# IFE_TSAL_Light_2019_v1_0.net
KiCad netlist of a schematic drawn in EAGLE
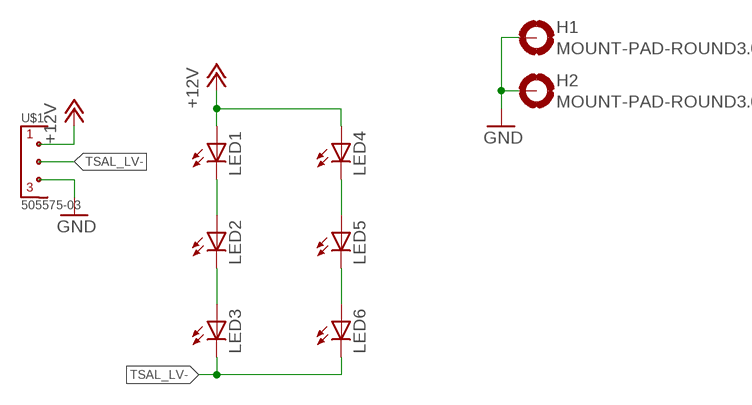
[diagram p0: schematic, sheet 1]

(export (version "E")
  (design (tool "Eeschema 10.0.6"))
  (components
    (comp (ref "H1")
      (value "MOUNT-PAD-ROUND3.0")
      (footprint "eagle-import:3,0-PAD")
      (libsource (lib "eagle-import") (part "MOUNT-PAD-ROUND3.0"))
    )
    (comp (ref "H2")
      (value "MOUNT-PAD-ROUND3.0")
      (footprint "eagle-import:3,0-PAD")
      (libsource (lib "eagle-import") (part "MOUNT-PAD-ROUND3.0"))
    )
    (comp (ref "LED1")
      (value "LED5MM")
      (footprint "eagle-import:LED5MM")
      (libsource (lib "eagle-import") (part "LED5MM"))
    )
    (comp (ref "LED2")
      (value "LED5MM")
      (footprint "eagle-import:LED5MM")
      (libsource (lib "eagle-import") (part "LED5MM"))
    )
    (comp (ref "LED3")
      (value "LED5MM")
      (footprint "eagle-import:LED5MM")
      (libsource (lib "eagle-import") (part "LED5MM"))
    )
    (comp (ref "LED4")
      (value "LED5MM")
      (footprint "eagle-import:LED5MM")
      (libsource (lib "eagle-import") (part "LED5MM"))
    )
    (comp (ref "LED5")
      (value "LED5MM")
      (footprint "eagle-import:LED5MM")
      (libsource (lib "eagle-import") (part "LED5MM"))
    )
    (comp (ref "LED6")
      (value "LED5MM")
      (footprint "eagle-import:LED5MM")
      (libsource (lib "eagle-import") (part "LED5MM"))
    )
    (comp (ref "U$1")
      (value "505575-03")
      (footprint "eagle-import:505575-03")
      (libsource (lib "eagle-import") (part "505575-03"))
    )
  )
  (nets
    (net (code "1") (name "+12V") (class "Default")
      (node (ref "LED1") (pin "A") (pinfunction "A_A") (pintype "passive"))
      (node (ref "LED4") (pin "A") (pinfunction "A_A") (pintype "passive"))
      (node (ref "U$1") (pin "1") (pinfunction "1_1") (pintype "bidirectional"))
    )
    (net (code "2") (name "GND") (class "Default")
      (node (ref "H1") (pin "B3,0") (pinfunction "MOUNT_B3,0") (pintype "passive"))
      (node (ref "H2") (pin "B3,0") (pinfunction "MOUNT_B3,0") (pintype "passive"))
      (node (ref "U$1") (pin "3") (pinfunction "3_3") (pintype "bidirectional"))
    )
    (net (code "3") (name "Net-(LED1-C)") (class "Default")
      (node (ref "LED1") (pin "K") (pinfunction "C_K") (pintype "passive"))
      (node (ref "LED2") (pin "A") (pinfunction "A_A") (pintype "passive"))
    )
    (net (code "4") (name "Net-(LED2-C)") (class "Default")
      (node (ref "LED2") (pin "K") (pinfunction "C_K") (pintype "passive"))
      (node (ref "LED3") (pin "A") (pinfunction "A_A") (pintype "passive"))
    )
    (net (code "5") (name "Net-(LED4-C)") (class "Default")
      (node (ref "LED4") (pin "K") (pinfunction "C_K") (pintype "passive"))
      (node (ref "LED5") (pin "A") (pinfunction "A_A") (pintype "passive"))
    )
    (net (code "6") (name "Net-(LED5-C)") (class "Default")
      (node (ref "LED5") (pin "K") (pinfunction "C_K") (pintype "passive"))
      (node (ref "LED6") (pin "A") (pinfunction "A_A") (pintype "passive"))
    )
    (net (code "7") (name "TSAL_LV-") (class "Default")
      (node (ref "LED3") (pin "K") (pinfunction "C_K") (pintype "passive"))
      (node (ref "LED6") (pin "K") (pinfunction "C_K") (pintype "passive"))
      (node (ref "U$1") (pin "2") (pinfunction "2_2") (pintype "bidirectional"))
    )
  )
)
